# Tiny_5_Stick_SMD_-v5.net
KiCad netlist of a schematic drawn in EAGLE
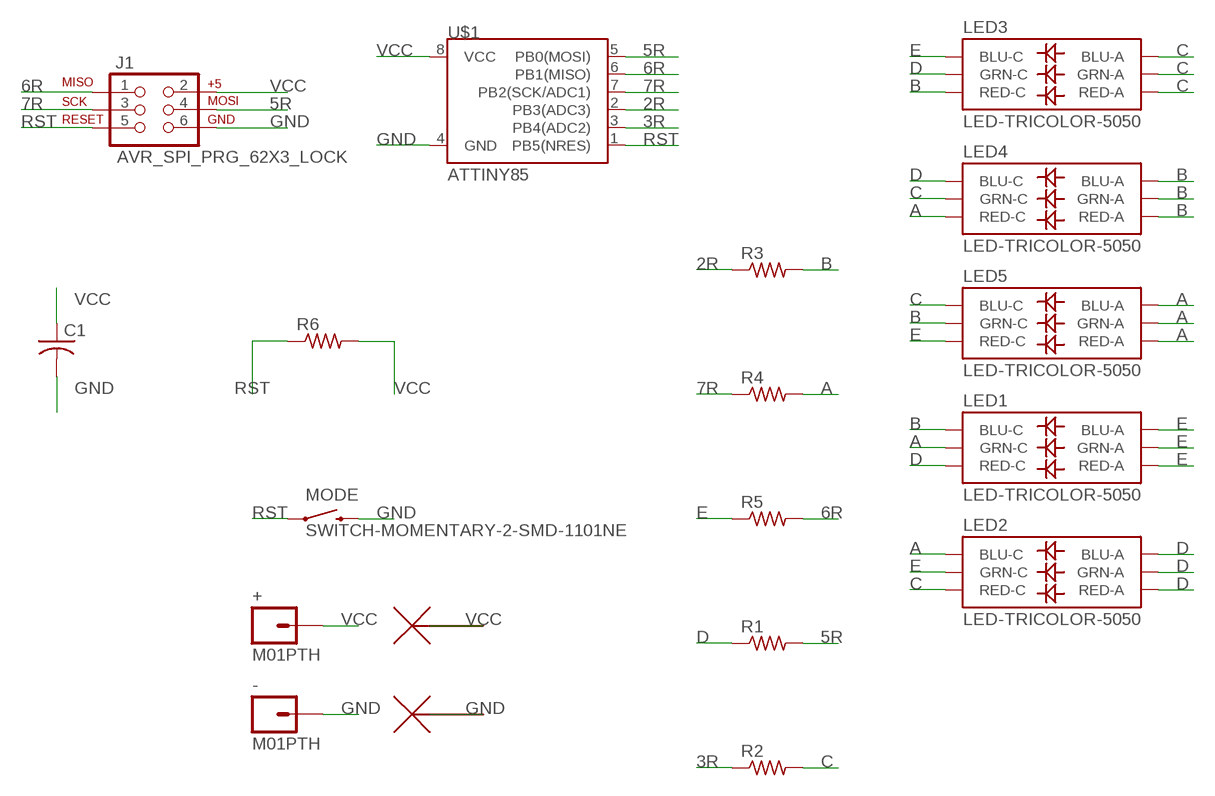
[diagram p0: schematic, sheet 1]

(export (version "E")
  (design (tool "Eeschema 10.0.6"))
  (components
    (comp (ref "+")
      (value "M01PTH")
      (footprint "eagle-import:1X01")
      (libsource (lib "eagle-import") (part "M01PTH"))
    )
    (comp (ref "-")
      (value "M01PTH")
      (footprint "eagle-import:1X01")
      (libsource (lib "eagle-import") (part "M01PTH"))
    )
    (comp (ref "C1")
      (value "C-USC0805K")
      (footprint "eagle-import:C0805K")
      (libsource (lib "eagle-import") (part "C-USC0805K"))
    )
    (comp (ref "GNDEXT")
      (value "M01")
      (footprint "eagle-import:3X1.75")
      (libsource (lib "eagle-import") (part "M01"))
    )
    (comp (ref "J1")
      (value "AVR_SPI_PRG_62X3_LOCK")
      (footprint "eagle-import:2X3_LOCK")
      (libsource (lib "eagle-import") (part "AVR_SPI_PRG_62X3_LOCK"))
    )
    (comp (ref "LED1")
      (value "LED-TRICOLOR-5050")
      (footprint "eagle-import:LED-TRICOLOR-5050")
      (libsource (lib "eagle-import") (part "LED-TRICOLOR-5050"))
    )
    (comp (ref "LED2")
      (value "LED-TRICOLOR-5050")
      (footprint "eagle-import:LED-TRICOLOR-5050")
      (libsource (lib "eagle-import") (part "LED-TRICOLOR-5050"))
    )
    (comp (ref "LED3")
      (value "LED-TRICOLOR-5050")
      (footprint "eagle-import:LED-TRICOLOR-5050")
      (libsource (lib "eagle-import") (part "LED-TRICOLOR-5050"))
    )
    (comp (ref "LED4")
      (value "LED-TRICOLOR-5050")
      (footprint "eagle-import:LED-TRICOLOR-5050")
      (libsource (lib "eagle-import") (part "LED-TRICOLOR-5050"))
    )
    (comp (ref "LED5")
      (value "LED-TRICOLOR-5050")
      (footprint "eagle-import:LED-TRICOLOR-5050")
      (libsource (lib "eagle-import") (part "LED-TRICOLOR-5050"))
    )
    (comp (ref "MODE")
      (value "SWITCH-MOMENTARY-2-SMD-1101NE")
      (footprint "eagle-import:TACTILE-SWITCH-1101NE")
      (libsource (lib "eagle-import") (part "SWITCH-MOMENTARY-2-SMD-1101NE"))
    )
    (comp (ref "R1")
      (value "R-US_M0805")
      (footprint "eagle-import:M0805")
      (libsource (lib "eagle-import") (part "R-US_M0805"))
    )
    (comp (ref "R2")
      (value "R-US_M0805")
      (footprint "eagle-import:M0805")
      (libsource (lib "eagle-import") (part "R-US_M0805"))
    )
    (comp (ref "R3")
      (value "R-US_M0805")
      (footprint "eagle-import:M0805")
      (libsource (lib "eagle-import") (part "R-US_M0805"))
    )
    (comp (ref "R4")
      (value "R-US_M0805")
      (footprint "eagle-import:M0805")
      (libsource (lib "eagle-import") (part "R-US_M0805"))
    )
    (comp (ref "R5")
      (value "R-US_M0805")
      (footprint "eagle-import:M0805")
      (libsource (lib "eagle-import") (part "R-US_M0805"))
    )
    (comp (ref "R6")
      (value "R-US_M0805")
      (footprint "eagle-import:M0805")
      (libsource (lib "eagle-import") (part "R-US_M0805"))
    )
    (comp (ref "U$1")
      (value "ATTINY85")
      (footprint "eagle-import:SO08-EIAJ")
      (libsource (lib "eagle-import") (part "ATTINY45"))
    )
    (comp (ref "VCCEXT")
      (value "M01")
      (footprint "eagle-import:3X1.75")
      (libsource (lib "eagle-import") (part "M01"))
    )
  )
  (nets
    (net (code "1") (name "/2R") (class "Default")
      (node (ref "R3") (pin "1") (pinfunction "1_1") (pintype "passive"))
      (node (ref "U$1") (pin "2") (pinfunction "PB3(ADC3)_2") (pintype "bidirectional"))
    )
    (net (code "2") (name "/3R") (class "Default")
      (node (ref "R2") (pin "1") (pinfunction "1_1") (pintype "passive"))
      (node (ref "U$1") (pin "3") (pinfunction "PB4(ADC2)_3") (pintype "bidirectional"))
    )
    (net (code "3") (name "/5R") (class "Default")
      (node (ref "J1") (pin "4") (pinfunction "4_4") (pintype "passive"))
      (node (ref "R1") (pin "2") (pinfunction "2_2") (pintype "passive"))
      (node (ref "U$1") (pin "5") (pinfunction "PB0(MOSI)_5") (pintype "bidirectional"))
    )
    (net (code "4") (name "/6R") (class "Default")
      (node (ref "J1") (pin "1") (pinfunction "1_1") (pintype "passive"))
      (node (ref "R5") (pin "2") (pinfunction "2_2") (pintype "passive"))
      (node (ref "U$1") (pin "6") (pinfunction "PB1(MISO)_6") (pintype "bidirectional"))
    )
    (net (code "5") (name "/7R") (class "Default")
      (node (ref "J1") (pin "3") (pinfunction "3_3") (pintype "passive"))
      (node (ref "R4") (pin "1") (pinfunction "1_1") (pintype "passive"))
      (node (ref "U$1") (pin "7") (pinfunction "PB2(SCK/ADC1)_7") (pintype "bidirectional"))
    )
    (net (code "6") (name "/A") (class "Default")
      (node (ref "LED1") (pin "4") (pinfunction "GRN-C_4") (pintype "bidirectional"))
      (node (ref "LED2") (pin "6") (pinfunction "BLU-C_6") (pintype "bidirectional"))
      (node (ref "LED4") (pin "5") (pinfunction "RED-C_5") (pintype "bidirectional"))
      (node (ref "LED5") (pin "1") (pinfunction "BLU-A_1") (pintype "bidirectional"))
      (node (ref "LED5") (pin "2") (pinfunction "RED-A_2") (pintype "bidirectional"))
      (node (ref "LED5") (pin "3") (pinfunction "GRN-A_3") (pintype "bidirectional"))
      (node (ref "R4") (pin "2") (pinfunction "2_2") (pintype "passive"))
    )
    (net (code "7") (name "/B") (class "Default")
      (node (ref "LED1") (pin "6") (pinfunction "BLU-C_6") (pintype "bidirectional"))
      (node (ref "LED3") (pin "5") (pinfunction "RED-C_5") (pintype "bidirectional"))
      (node (ref "LED4") (pin "1") (pinfunction "BLU-A_1") (pintype "bidirectional"))
      (node (ref "LED4") (pin "2") (pinfunction "RED-A_2") (pintype "bidirectional"))
      (node (ref "LED4") (pin "3") (pinfunction "GRN-A_3") (pintype "bidirectional"))
      (node (ref "LED5") (pin "4") (pinfunction "GRN-C_4") (pintype "bidirectional"))
      (node (ref "R3") (pin "2") (pinfunction "2_2") (pintype "passive"))
    )
    (net (code "8") (name "/C") (class "Default")
      (node (ref "LED2") (pin "5") (pinfunction "RED-C_5") (pintype "bidirectional"))
      (node (ref "LED3") (pin "1") (pinfunction "BLU-A_1") (pintype "bidirectional"))
      (node (ref "LED3") (pin "2") (pinfunction "RED-A_2") (pintype "bidirectional"))
      (node (ref "LED3") (pin "3") (pinfunction "GRN-A_3") (pintype "bidirectional"))
      (node (ref "LED4") (pin "4") (pinfunction "GRN-C_4") (pintype "bidirectional"))
      (node (ref "LED5") (pin "6") (pinfunction "BLU-C_6") (pintype "bidirectional"))
      (node (ref "R2") (pin "2") (pinfunction "2_2") (pintype "passive"))
    )
    (net (code "9") (name "/D") (class "Default")
      (node (ref "LED1") (pin "5") (pinfunction "RED-C_5") (pintype "bidirectional"))
      (node (ref "LED2") (pin "1") (pinfunction "BLU-A_1") (pintype "bidirectional"))
      (node (ref "LED2") (pin "2") (pinfunction "RED-A_2") (pintype "bidirectional"))
      (node (ref "LED2") (pin "3") (pinfunction "GRN-A_3") (pintype "bidirectional"))
      (node (ref "LED3") (pin "4") (pinfunction "GRN-C_4") (pintype "bidirectional"))
      (node (ref "LED4") (pin "6") (pinfunction "BLU-C_6") (pintype "bidirectional"))
      (node (ref "R1") (pin "1") (pinfunction "1_1") (pintype "passive"))
    )
    (net (code "10") (name "/E") (class "Default")
      (node (ref "LED1") (pin "1") (pinfunction "BLU-A_1") (pintype "bidirectional"))
      (node (ref "LED1") (pin "2") (pinfunction "RED-A_2") (pintype "bidirectional"))
      (node (ref "LED1") (pin "3") (pinfunction "GRN-A_3") (pintype "bidirectional"))
      (node (ref "LED2") (pin "4") (pinfunction "GRN-C_4") (pintype "bidirectional"))
      (node (ref "LED3") (pin "6") (pinfunction "BLU-C_6") (pintype "bidirectional"))
      (node (ref "LED5") (pin "5") (pinfunction "RED-C_5") (pintype "bidirectional"))
      (node (ref "R5") (pin "1") (pinfunction "1_1") (pintype "passive"))
    )
    (net (code "11") (name "/GND") (class "Default")
      (node (ref "-") (pin "1") (pinfunction "1_1") (pintype "passive"))
      (node (ref "C1") (pin "2") (pinfunction "2_2") (pintype "passive"))
      (node (ref "GNDEXT") (pin "P$1") (pinfunction "P$1_P$1") (pintype "bidirectional"))
      (node (ref "J1") (pin "6") (pinfunction "6_6") (pintype "passive"))
      (node (ref "MODE") (pin "P$2") (pinfunction "2_P$2") (pintype "passive"))
      (node (ref "U$1") (pin "4") (pinfunction "GND_4") (pintype "bidirectional"))
    )
    (net (code "12") (name "/RST") (class "Default")
      (node (ref "J1") (pin "5") (pinfunction "5_5") (pintype "passive"))
      (node (ref "MODE") (pin "P$1") (pinfunction "1_P$1") (pintype "passive"))
      (node (ref "R6") (pin "1") (pinfunction "1_1") (pintype "passive"))
      (node (ref "U$1") (pin "1") (pinfunction "PB5(NRES)_1") (pintype "bidirectional"))
    )
    (net (code "13") (name "/VCC") (class "Default")
      (node (ref "+") (pin "1") (pinfunction "1_1") (pintype "passive"))
      (node (ref "C1") (pin "1") (pinfunction "1_1") (pintype "passive"))
      (node (ref "J1") (pin "2") (pinfunction "2_2") (pintype "passive"))
      (node (ref "R6") (pin "2") (pinfunction "2_2") (pintype "passive"))
      (node (ref "U$1") (pin "8") (pinfunction "VCC_8") (pintype "bidirectional"))
      (node (ref "VCCEXT") (pin "P$1") (pinfunction "P$1_P$1") (pintype "bidirectional"))
    )
  )
)
